# Sway.net
KiCad netlist of a schematic drawn in EAGLE
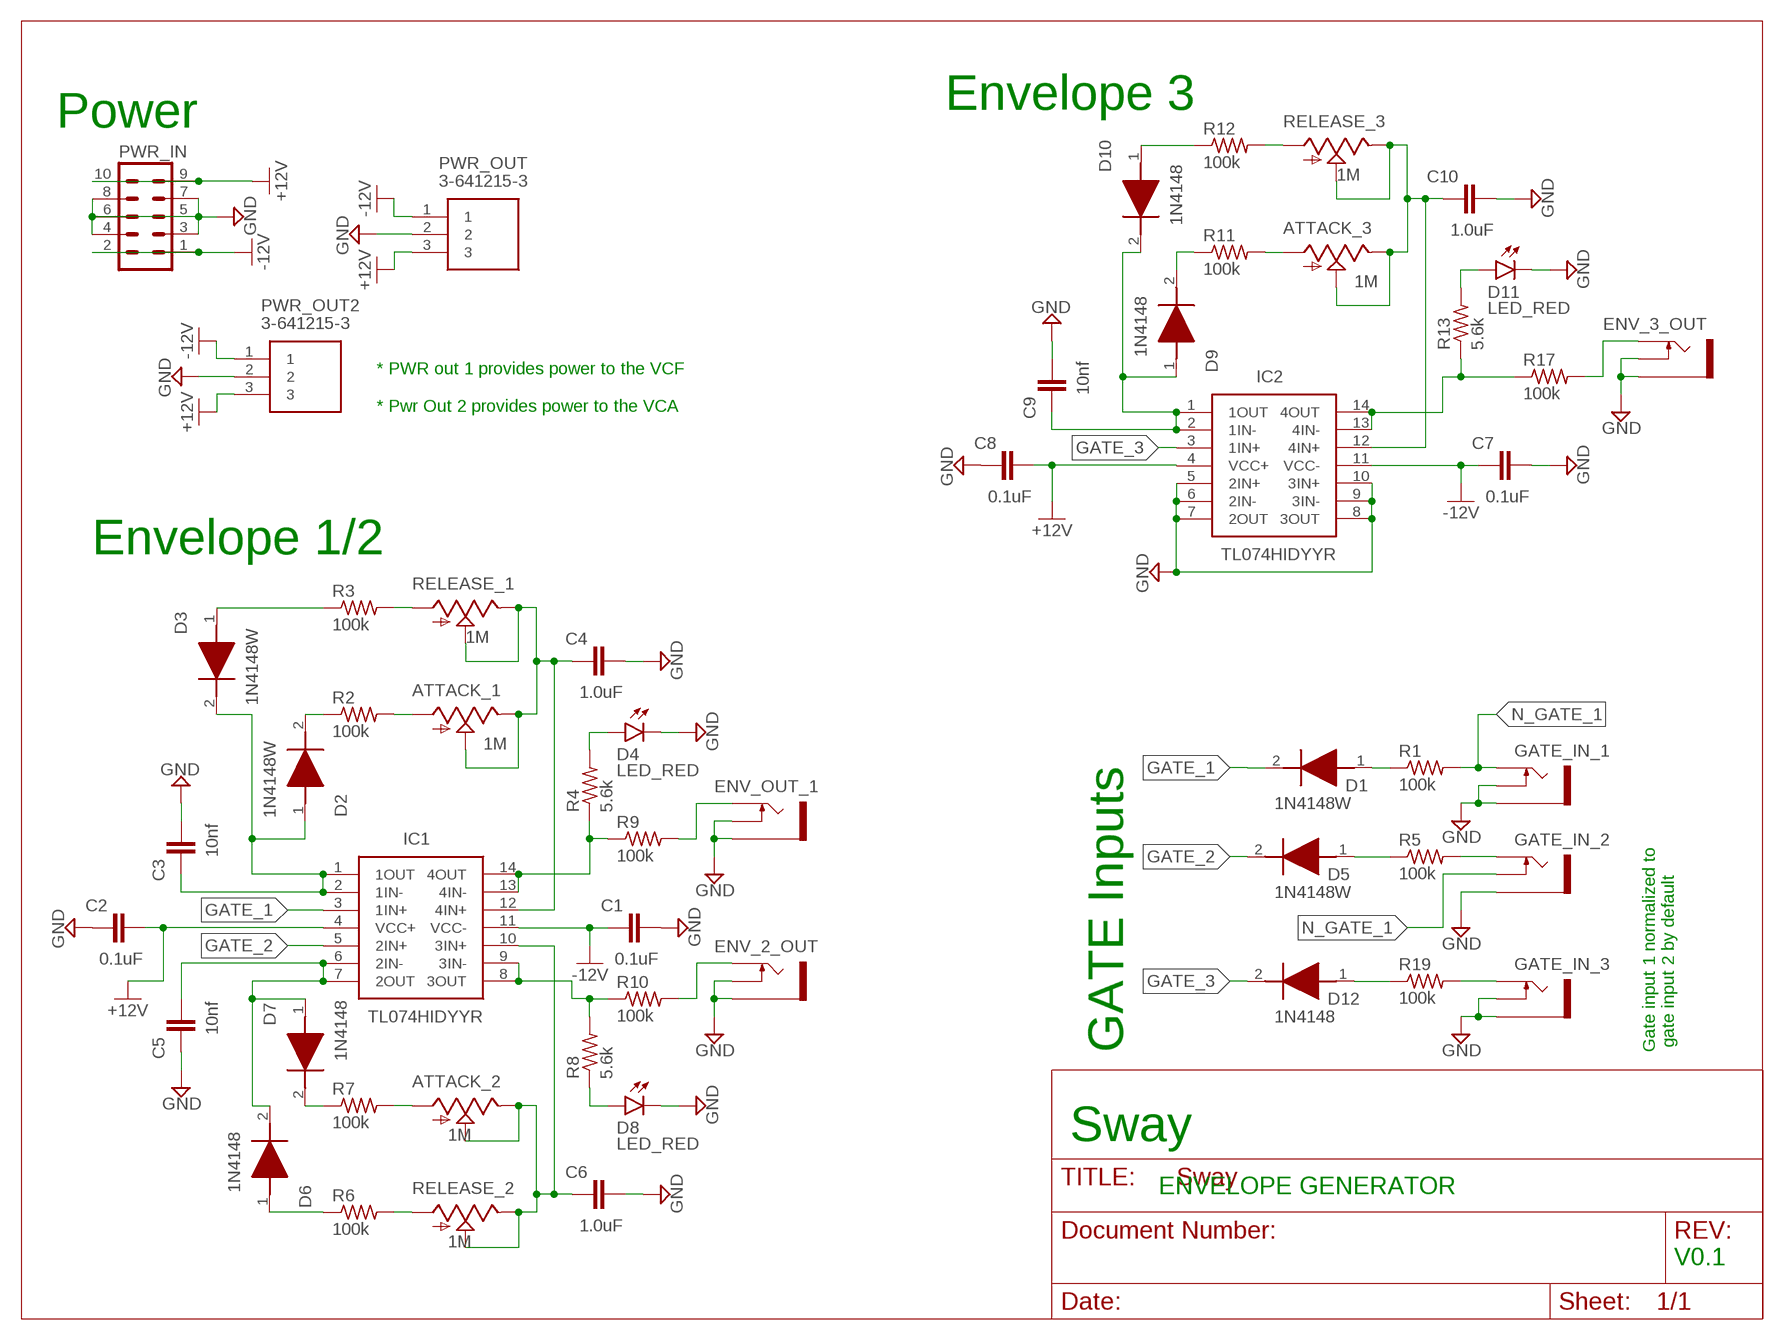
[diagram p0: schematic, sheet 1]

(export (version "E")
  (design (tool "Eeschema 10.0.6"))
  (components
    (comp (ref "ATTACK_1")
      (value "1M")
      (footprint "eagle-import:9MM_SNAP-IN_POT")
      (libsource (lib "eagle-import") (part "9MM_SNAP-IN_POT_"))
    )
    (comp (ref "ATTACK_2")
      (value "1M")
      (footprint "eagle-import:9MM_SNAP-IN_POT")
      (libsource (lib "eagle-import") (part "9MM_SNAP-IN_POT_"))
    )
    (comp (ref "ATTACK_3")
      (value "1M")
      (footprint "eagle-import:9MM_SNAP-IN_POT")
      (libsource (lib "eagle-import") (part "9MM_SNAP-IN_POT_"))
    )
    (comp (ref "C1")
      (value "0.1uF")
      (footprint "eagle-import:0402")
      (libsource (lib "eagle-import") (part "0.1UF-0402-16V-10%"))
    )
    (comp (ref "C2")
      (value "0.1uF")
      (footprint "eagle-import:0402")
      (libsource (lib "eagle-import") (part "0.1UF-0402-16V-10%"))
    )
    (comp (ref "C3")
      (value "10nf")
      (footprint "eagle-import:0402")
      (libsource (lib "eagle-import") (part "0.1UF-0402-16V-10%"))
    )
    (comp (ref "C4")
      (value "1.0uF")
      (footprint "eagle-import:0402")
      (libsource (lib "eagle-import") (part "1.0UF-0402-16V-10%"))
    )
    (comp (ref "C5")
      (value "10nf")
      (footprint "eagle-import:0402")
      (libsource (lib "eagle-import") (part "0.1UF-0402-16V-10%"))
    )
    (comp (ref "C6")
      (value "1.0uF")
      (footprint "eagle-import:0402")
      (libsource (lib "eagle-import") (part "1.0UF-0402-16V-10%"))
    )
    (comp (ref "C7")
      (value "0.1uF")
      (footprint "eagle-import:0402")
      (libsource (lib "eagle-import") (part "0.1UF-0402-16V-10%"))
    )
    (comp (ref "C8")
      (value "0.1uF")
      (footprint "eagle-import:0402")
      (libsource (lib "eagle-import") (part "0.1UF-0402-16V-10%"))
    )
    (comp (ref "C9")
      (value "10nf")
      (footprint "eagle-import:0402")
      (libsource (lib "eagle-import") (part "0.1UF-0402-16V-10%"))
    )
    (comp (ref "C10")
      (value "1.0uF")
      (footprint "eagle-import:0402")
      (libsource (lib "eagle-import") (part "1.0UF-0402-16V-10%"))
    )
    (comp (ref "D1")
      (value "1N4148W")
      (footprint "eagle-import:SOD3716X135N")
      (fields
        (field (name "MANUFACTURER_PART_NUMBER") "1N4148W-HG3_A-08")
        (field (name "MOUSER_PART_NUMBER") "78-1N4148W-HG3_A-08")
      )
      (libsource (lib "eagle-import") (part "1N4148W-HG3_A-08"))
    )
    (comp (ref "D2")
      (value "1N4148W")
      (footprint "eagle-import:SOD3716X135N")
      (fields
        (field (name "MANUFACTURER_PART_NUMBER") "1N4148W-HG3_A-08")
        (field (name "MOUSER_PART_NUMBER") "78-1N4148W-HG3_A-08")
      )
      (libsource (lib "eagle-import") (part "1N4148W-HG3_A-08"))
    )
    (comp (ref "D3")
      (value "1N4148W")
      (footprint "eagle-import:SOD3716X135N")
      (fields
        (field (name "MANUFACTURER_PART_NUMBER") "1N4148W-HG3_A-08")
        (field (name "MOUSER_PART_NUMBER") "78-1N4148W-HG3_A-08")
      )
      (libsource (lib "eagle-import") (part "1N4148W-HG3_A-08"))
    )
    (comp (ref "D4")
      (value "LED_RED")
      (footprint "eagle-import:LEDRD254W60D565H860B")
      (libsource (lib "eagle-import") (part "LED_RADIALRED_"))
    )
    (comp (ref "D5")
      (value "1N4148W")
      (footprint "eagle-import:SOD3716X135N")
      (fields
        (field (name "MANUFACTURER_PART_NUMBER") "1N4148W-HG3_A-08")
        (field (name "MOUSER_PART_NUMBER") "78-1N4148W-HG3_A-08")
      )
      (libsource (lib "eagle-import") (part "1N4148W-HG3_A-08"))
    )
    (comp (ref "D6")
      (value "1N4148")
      (footprint "eagle-import:SOD3716X135N")
      (fields
        (field (name "MANUFACTURER_PART_NUMBER") "1N4148W-HG3_A-08")
        (field (name "MOUSER_PART_NUMBER") "78-1N4148W-HG3_A-08")
      )
      (libsource (lib "eagle-import") (part "1N4148W-HG3_A-08"))
    )
    (comp (ref "D7")
      (value "1N4148")
      (footprint "eagle-import:SOD3716X135N")
      (fields
        (field (name "MANUFACTURER_PART_NUMBER") "1N4148W-HG3_A-08")
        (field (name "MOUSER_PART_NUMBER") "78-1N4148W-HG3_A-08")
      )
      (libsource (lib "eagle-import") (part "1N4148W-HG3_A-08"))
    )
    (comp (ref "D8")
      (value "LED_RED")
      (footprint "eagle-import:LEDRD254W60D565H860B")
      (libsource (lib "eagle-import") (part "LED_RADIALRED_"))
    )
    (comp (ref "D9")
      (value "1N4148")
      (footprint "eagle-import:SOD3716X135N")
      (fields
        (field (name "MANUFACTURER_PART_NUMBER") "1N4148W-HG3_A-08")
        (field (name "MOUSER_PART_NUMBER") "78-1N4148W-HG3_A-08")
      )
      (libsource (lib "eagle-import") (part "1N4148W-HG3_A-08"))
    )
    (comp (ref "D10")
      (value "1N4148")
      (footprint "eagle-import:SOD3716X135N")
      (fields
        (field (name "MANUFACTURER_PART_NUMBER") "1N4148W-HG3_A-08")
        (field (name "MOUSER_PART_NUMBER") "78-1N4148W-HG3_A-08")
      )
      (libsource (lib "eagle-import") (part "1N4148W-HG3_A-08"))
    )
    (comp (ref "D11")
      (value "LED_RED")
      (footprint "eagle-import:LEDRD254W60D565H860B")
      (libsource (lib "eagle-import") (part "LED_RADIALRED_"))
    )
    (comp (ref "D12")
      (value "1N4148")
      (footprint "eagle-import:SOD3716X135N")
      (fields
        (field (name "MANUFACTURER_PART_NUMBER") "1N4148W-HG3_A-08")
        (field (name "MOUSER_PART_NUMBER") "78-1N4148W-HG3_A-08")
      )
      (libsource (lib "eagle-import") (part "1N4148W-HG3_A-08"))
    )
    (comp (ref "ENV_2_OUT")
      (value "THONKICONNNEW")
      (footprint "eagle-import:WQP-PJ301M-12_JACK")
      (fields
        (field (name "SPICEMODEL") "GATE_IN_1")
        (field (name "SPICEMODELTEXT") "**********************\\n* Autodesk EAGLE - SPICE Model File\\n* Author:\\n* Date: \\n**********************\\n.SUBCKT GATE_IN_1 T S SW\\n* Assume normally closed switch (SW → T when unplugged)\\n* Always connect sleeve\\nRsleeve S 0 0.001\\n* Connect switch to tip if no plug\\nRnorm SW T 1\\n* Patch cable overrides switch (comment one of these in/out based on mode)\\nRpatched TIP_SRC T 0.001\\n.ENDS GATE_IN_1")
        (field (name "SPICEPREFIX") "X")
      )
      (libsource (lib "eagle-import") (part "THONKICONNNEW"))
    )
    (comp (ref "ENV_3_OUT")
      (value "THONKICONNNEW")
      (footprint "eagle-import:WQP-PJ301M-12_JACK")
      (fields
        (field (name "SPICEMODEL") "GATE_IN_1")
        (field (name "SPICEMODELTEXT") "**********************\\n* Autodesk EAGLE - SPICE Model File\\n* Author:\\n* Date: \\n**********************\\n.SUBCKT GATE_IN_1 T S SW\\n* Assume normally closed switch (SW → T when unplugged)\\n* Always connect sleeve\\nRsleeve S 0 0.001\\n* Connect switch to tip if no plug\\nRnorm SW T 1\\n* Patch cable overrides switch (comment one of these in/out based on mode)\\nRpatched TIP_SRC T 0.001\\n.ENDS GATE_IN_1")
        (field (name "SPICEPREFIX") "X")
      )
      (libsource (lib "eagle-import") (part "THONKICONNNEW"))
    )
    (comp (ref "ENV_OUT_1")
      (value "THONKICONNNEW")
      (footprint "eagle-import:WQP-PJ301M-12_JACK")
      (libsource (lib "eagle-import") (part "THONKICONNNEW"))
    )
    (comp (ref "GATE_IN_1")
      (value "THONKICONNNEW")
      (footprint "eagle-import:WQP-PJ301M-12_JACK")
      (fields
        (field (name "SPICEMODEL") "GATE_IN_1")
        (field (name "SPICEMODELTEXT") "**********************\\n* Autodesk EAGLE - SPICE Model File\\n* Author:\\n* Date: \\n**********************\\n.SUBCKT GATE_IN_1 T S SW\\n* Assume normally closed switch (SW → T when unplugged)\\n* Always connect sleeve\\nRsleeve S 0 0.001\\n* Connect switch to tip if no plug\\nRnorm SW T 1\\n* Patch cable overrides switch (comment one of these in/out based on mode)\\nRpatched TIP_SRC T 0.001\\n.ENDS GATE_IN_1")
        (field (name "SPICEPREFIX") "X")
      )
      (libsource (lib "eagle-import") (part "THONKICONNNEW"))
    )
    (comp (ref "GATE_IN_2")
      (value "THONKICONNNEW")
      (footprint "eagle-import:WQP-PJ301M-12_JACK")
      (fields
        (field (name "SPICEMODEL") "GATE_IN_1")
        (field (name "SPICEMODELTEXT") "**********************\\n* Autodesk EAGLE - SPICE Model File\\n* Author:\\n* Date: \\n**********************\\n.SUBCKT GATE_IN_1 T S SW\\n* Assume normally closed switch (SW → T when unplugged)\\n* Always connect sleeve\\nRsleeve S 0 0.001\\n* Connect switch to tip if no plug\\nRnorm SW T 1\\n* Patch cable overrides switch (comment one of these in/out based on mode)\\nRpatched TIP_SRC T 0.001\\n.ENDS GATE_IN_1")
        (field (name "SPICEPREFIX") "X")
      )
      (libsource (lib "eagle-import") (part "THONKICONNNEW"))
    )
    (comp (ref "GATE_IN_3")
      (value "THONKICONNNEW")
      (footprint "eagle-import:WQP-PJ301M-12_JACK")
      (fields
        (field (name "SPICEMODEL") "GATE_IN_1")
        (field (name "SPICEMODELTEXT") "**********************\\n* Autodesk EAGLE - SPICE Model File\\n* Author:\\n* Date: \\n**********************\\n.SUBCKT GATE_IN_1 T S SW\\n* Assume normally closed switch (SW → T when unplugged)\\n* Always connect sleeve\\nRsleeve S 0 0.001\\n* Connect switch to tip if no plug\\nRnorm SW T 1\\n* Patch cable overrides switch (comment one of these in/out based on mode)\\nRpatched TIP_SRC T 0.001\\n.ENDS GATE_IN_1")
        (field (name "SPICEPREFIX") "X")
      )
      (libsource (lib "eagle-import") (part "THONKICONNNEW"))
    )
    (comp (ref "IC1")
      (value "TL074HIDYYR")
      (footprint "eagle-import:SOP50P326X110-14N")
      (fields (field (name "MOUSER_PART_NUMBER") "595-TL074HIDYYR"))
      (libsource (lib "eagle-import") (part "TL074HIDYYR"))
    )
    (comp (ref "IC2")
      (value "TL074HIDYYR")
      (footprint "eagle-import:SOP50P326X110-14N")
      (fields (field (name "MOUSER_PART_NUMBER") "595-TL074HIDYYR"))
      (libsource (lib "eagle-import") (part "TL074HIDYYR"))
    )
    (comp (ref "PWR_IN")
      (value "EURO_POWER_HEADERREGULAR")
      (footprint "eagle-import:EURO_POWER_HEADER")
      (libsource (lib "eagle-import") (part "EURO_POWER_HEADERREGULAR"))
    )
    (comp (ref "PWR_OUT")
      (value "3-641215-3")
      (footprint "eagle-import:SHDR3W66P0X254_1X3_762X572X104")
      (fields
        (field (name "MOUSER_PART_NUMBER") "571-3-641215-3")
        (field (name "SPICEMODEL") "PWR_OUT")
        (field (name "SPICEMODELTEXT") "**********************\\n* Autodesk EAGLE - SPICE Model File\\n* Author:\\n* Date: \\n**********************\\n.SUBCKT PWR_OUT 1 2 3\\n* Pin 1 = -12V\\n* Pin 2 = GND\\n* Pin 3 = +12V\\n* Tie pins to global rails\\nRout1 1 VNEG 0.001\\nRout2 2 0   0.001\\nRout3 3 VPOS 0.001\\n.ENDS PWR_OUT")
        (field (name "SPICEPREFIX") "X")
      )
      (libsource (lib "eagle-import") (part "3-641215-3"))
    )
    (comp (ref "PWR_OUT2")
      (value "3-641215-3")
      (footprint "eagle-import:SHDR3W66P0X254_1X3_762X572X104")
      (fields
        (field (name "MOUSER_PART_NUMBER") "571-3-641215-3")
        (field (name "SPICEMODEL") "PWR_OUT")
        (field (name "SPICEMODELTEXT") "**********************\\n* Autodesk EAGLE - SPICE Model File\\n* Author:\\n* Date: \\n**********************\\n.SUBCKT PWR_OUT 1 2 3\\n* Pin 1 = -12V\\n* Pin 2 = GND\\n* Pin 3 = +12V\\n* Tie pins to global rails\\nRout1 1 VNEG 0.001\\nRout2 2 0   0.001\\nRout3 3 VPOS 0.001\\n.ENDS PWR_OUT")
        (field (name "SPICEPREFIX") "X")
      )
      (libsource (lib "eagle-import") (part "3-641215-3"))
    )
    (comp (ref "R1")
      (value "100k")
      (footprint "eagle-import:RESC1005X40")
      (libsource (lib "eagle-import") (part "R-USCHIP-0402(1005-METRIC)_"))
    )
    (comp (ref "R2")
      (value "100k")
      (footprint "eagle-import:RESC1005X40")
      (libsource (lib "eagle-import") (part "R-USCHIP-0402(1005-METRIC)_"))
    )
    (comp (ref "R3")
      (value "100k")
      (footprint "eagle-import:RESC1005X40")
      (libsource (lib "eagle-import") (part "R-USCHIP-0402(1005-METRIC)_"))
    )
    (comp (ref "R4")
      (value "5.6k")
      (footprint "eagle-import:RESC1005X40")
      (libsource (lib "eagle-import") (part "R-USCHIP-0402(1005-METRIC)_"))
    )
    (comp (ref "R5")
      (value "100k")
      (footprint "eagle-import:RESC1005X40")
      (libsource (lib "eagle-import") (part "R-USCHIP-0402(1005-METRIC)_"))
    )
    (comp (ref "R6")
      (value "100k")
      (footprint "eagle-import:RESC1005X40")
      (libsource (lib "eagle-import") (part "R-USCHIP-0402(1005-METRIC)_"))
    )
    (comp (ref "R7")
      (value "100k")
      (footprint "eagle-import:RESC1005X40")
      (libsource (lib "eagle-import") (part "R-USCHIP-0402(1005-METRIC)_"))
    )
    (comp (ref "R8")
      (value "5.6k")
      (footprint "eagle-import:RESC1005X40")
      (libsource (lib "eagle-import") (part "R-USCHIP-0402(1005-METRIC)_"))
    )
    (comp (ref "R9")
      (value "100k")
      (footprint "eagle-import:RESC1005X40")
      (libsource (lib "eagle-import") (part "R-USCHIP-0402(1005-METRIC)_"))
    )
    (comp (ref "R10")
      (value "100k")
      (footprint "eagle-import:RESC1005X40")
      (libsource (lib "eagle-import") (part "R-USCHIP-0402(1005-METRIC)_"))
    )
    (comp (ref "R11")
      (value "100k")
      (footprint "eagle-import:RESC1005X40")
      (libsource (lib "eagle-import") (part "R-USCHIP-0402(1005-METRIC)_"))
    )
    (comp (ref "R12")
      (value "100k")
      (footprint "eagle-import:RESC1005X40")
      (libsource (lib "eagle-import") (part "R-USCHIP-0402(1005-METRIC)_"))
    )
    (comp (ref "R13")
      (value "5.6k")
      (footprint "eagle-import:RESC1005X40")
      (libsource (lib "eagle-import") (part "R-USCHIP-0402(1005-METRIC)_"))
    )
    (comp (ref "R17")
      (value "100k")
      (footprint "eagle-import:RESC1005X40")
      (libsource (lib "eagle-import") (part "R-USCHIP-0402(1005-METRIC)_"))
    )
    (comp (ref "R19")
      (value "100k")
      (footprint "eagle-import:RESC1005X40")
      (libsource (lib "eagle-import") (part "R-USCHIP-0402(1005-METRIC)_"))
    )
    (comp (ref "RELEASE_1")
      (value "1M")
      (footprint "eagle-import:9MM_SNAP-IN_POT")
      (libsource (lib "eagle-import") (part "9MM_SNAP-IN_POT_"))
    )
    (comp (ref "RELEASE_2")
      (value "1M")
      (footprint "eagle-import:9MM_SNAP-IN_POT")
      (libsource (lib "eagle-import") (part "9MM_SNAP-IN_POT_"))
    )
    (comp (ref "RELEASE_3")
      (value "1M")
      (footprint "eagle-import:9MM_SNAP-IN_POT")
      (libsource (lib "eagle-import") (part "9MM_SNAP-IN_POT_"))
    )
  )
  (nets
    (net (code "1") (name "+12V") (class "Default")
      (node (ref "C2") (pin "2") (pinfunction "2_2") (pintype "passive"))
      (node (ref "C8") (pin "2") (pinfunction "2_2") (pintype "passive"))
      (node (ref "IC1") (pin "4") (pinfunction "VCC+_4") (pintype "bidirectional"))
      (node (ref "IC2") (pin "4") (pinfunction "VCC+_4") (pintype "bidirectional"))
      (node (ref "PWR_IN") (pin "10") (pinfunction "10_10") (pintype "passive"))
      (node (ref "PWR_IN") (pin "9") (pinfunction "9_9") (pintype "passive"))
      (node (ref "PWR_OUT") (pin "3") (pinfunction "3_3") (pintype "bidirectional"))
      (node (ref "PWR_OUT2") (pin "3") (pinfunction "3_3") (pintype "bidirectional"))
    )
    (net (code "2") (name "-12V") (class "Default")
      (node (ref "C1") (pin "1") (pinfunction "1_1") (pintype "passive"))
      (node (ref "C7") (pin "1") (pinfunction "1_1") (pintype "passive"))
      (node (ref "IC1") (pin "11") (pinfunction "VCC-_11") (pintype "bidirectional"))
      (node (ref "IC2") (pin "11") (pinfunction "VCC-_11") (pintype "bidirectional"))
      (node (ref "PWR_IN") (pin "1") (pinfunction "1_1") (pintype "passive"))
      (node (ref "PWR_IN") (pin "2") (pinfunction "2_2") (pintype "passive"))
      (node (ref "PWR_OUT") (pin "1") (pinfunction "1_1") (pintype "bidirectional"))
      (node (ref "PWR_OUT2") (pin "1") (pinfunction "1_1") (pintype "bidirectional"))
    )
    (net (code "3") (name "GATE_1") (class "Default")
      (node (ref "D1") (pin "2") (pinfunction "K_2") (pintype "bidirectional"))
      (node (ref "IC1") (pin "3") (pinfunction "1IN+_3") (pintype "bidirectional"))
    )
    (net (code "4") (name "GATE_2") (class "Default")
      (node (ref "D5") (pin "2") (pinfunction "K_2") (pintype "bidirectional"))
      (node (ref "IC1") (pin "5") (pinfunction "2IN+_5") (pintype "bidirectional"))
    )
    (net (code "5") (name "GATE_3") (class "Default")
      (node (ref "D12") (pin "2") (pinfunction "K_2") (pintype "bidirectional"))
      (node (ref "IC2") (pin "3") (pinfunction "1IN+_3") (pintype "bidirectional"))
    )
    (net (code "6") (name "GND") (class "Default")
      (node (ref "C1") (pin "2") (pinfunction "2_2") (pintype "passive"))
      (node (ref "C10") (pin "2") (pinfunction "2_2") (pintype "passive"))
      (node (ref "C2") (pin "1") (pinfunction "1_1") (pintype "passive"))
      (node (ref "C3") (pin "2") (pinfunction "2_2") (pintype "passive"))
      (node (ref "C4") (pin "2") (pinfunction "2_2") (pintype "passive"))
      (node (ref "C5") (pin "1") (pinfunction "1_1") (pintype "passive"))
      (node (ref "C6") (pin "2") (pinfunction "2_2") (pintype "passive"))
      (node (ref "C7") (pin "2") (pinfunction "2_2") (pintype "passive"))
      (node (ref "C8") (pin "1") (pinfunction "1_1") (pintype "passive"))
      (node (ref "C9") (pin "2") (pinfunction "2_2") (pintype "passive"))
      (node (ref "D11") (pin "2") (pinfunction "C_2") (pintype "passive"))
      (node (ref "D4") (pin "2") (pinfunction "C_2") (pintype "passive"))
      (node (ref "D8") (pin "2") (pinfunction "C_2") (pintype "passive"))
      (node (ref "ENV_2_OUT") (pin "P$2_SWITCH") (pinfunction "SWITCH_P$2_SWITCH") (pintype "passive"))
      (node (ref "ENV_2_OUT") (pin "P$3_SLEEVE") (pinfunction "SLEEVE_P$3_SLEEVE") (pintype "passive"))
      (node (ref "ENV_3_OUT") (pin "P$2_SWITCH") (pinfunction "SWITCH_P$2_SWITCH") (pintype "passive"))
      (node (ref "ENV_3_OUT") (pin "P$3_SLEEVE") (pinfunction "SLEEVE_P$3_SLEEVE") (pintype "passive"))
      (node (ref "ENV_OUT_1") (pin "P$2_SWITCH") (pinfunction "SWITCH_P$2_SWITCH") (pintype "passive"))
      (node (ref "ENV_OUT_1") (pin "P$3_SLEEVE") (pinfunction "SLEEVE_P$3_SLEEVE") (pintype "passive"))
      (node (ref "GATE_IN_1") (pin "P$2_SWITCH") (pinfunction "SWITCH_P$2_SWITCH") (pintype "passive"))
      (node (ref "GATE_IN_1") (pin "P$3_SLEEVE") (pinfunction "SLEEVE_P$3_SLEEVE") (pintype "passive"))
      (node (ref "GATE_IN_2") (pin "P$3_SLEEVE") (pinfunction "SLEEVE_P$3_SLEEVE") (pintype "passive"))
      (node (ref "GATE_IN_3") (pin "P$2_SWITCH") (pinfunction "SWITCH_P$2_SWITCH") (pintype "passive"))
      (node (ref "GATE_IN_3") (pin "P$3_SLEEVE") (pinfunction "SLEEVE_P$3_SLEEVE") (pintype "passive"))
      (node (ref "IC2") (pin "10") (pinfunction "3IN+_10") (pintype "bidirectional"))
      (node (ref "IC2") (pin "5") (pinfunction "2IN+_5") (pintype "bidirectional"))
      (node (ref "IC2") (pin "6") (pinfunction "2IN-_6") (pintype "bidirectional"))
      (node (ref "IC2") (pin "7") (pinfunction "2OUT_7") (pintype "bidirectional"))
      (node (ref "IC2") (pin "8") (pinfunction "3OUT_8") (pintype "bidirectional"))
      (node (ref "IC2") (pin "9") (pinfunction "3IN-_9") (pintype "bidirectional"))
      (node (ref "PWR_IN") (pin "3") (pinfunction "3_3") (pintype "passive"))
      (node (ref "PWR_IN") (pin "4") (pinfunction "4_4") (pintype "passive"))
      (node (ref "PWR_IN") (pin "5") (pinfunction "5_5") (pintype "passive"))
      (node (ref "PWR_IN") (pin "6") (pinfunction "6_6") (pintype "passive"))
      (node (ref "PWR_IN") (pin "7") (pinfunction "7_7") (pintype "passive"))
      (node (ref "PWR_IN") (pin "8") (pinfunction "8_8") (pintype "passive"))
      (node (ref "PWR_OUT") (pin "2") (pinfunction "2_2") (pintype "bidirectional"))
      (node (ref "PWR_OUT2") (pin "2") (pinfunction "2_2") (pintype "bidirectional"))
    )
    (net (code "7") (name "N_GATE_1") (class "Default")
      (node (ref "GATE_IN_1") (pin "P$1_TIP") (pinfunction "TIP_P$1_TIP") (pintype "passive"))
      (node (ref "GATE_IN_2") (pin "P$2_SWITCH") (pinfunction "SWITCH_P$2_SWITCH") (pintype "passive"))
      (node (ref "R1") (pin "2") (pinfunction "2_2") (pintype "passive"))
    )
    (net (code "8") (name "Net-(ATTACK_1-A)") (class "Default")
      (node (ref "ATTACK_1") (pin "1") (pinfunction "A_1") (pintype "passive"))
      (node (ref "R2") (pin "2") (pinfunction "2_2") (pintype "passive"))
    )
    (net (code "9") (name "Net-(ATTACK_1-E)") (class "Default")
      (node (ref "ATTACK_1") (pin "2") (pinfunction "S_2") (pintype "passive"))
      (node (ref "ATTACK_1") (pin "3") (pinfunction "E_3") (pintype "passive"))
      (node (ref "C4") (pin "1") (pinfunction "1_1") (pintype "passive"))
      (node (ref "IC1") (pin "12") (pinfunction "4IN+_12") (pintype "bidirectional"))
      (node (ref "RELEASE_1") (pin "2") (pinfunction "S_2") (pintype "passive"))
      (node (ref "RELEASE_1") (pin "3") (pinfunction "E_3") (pintype "passive"))
    )
    (net (code "10") (name "Net-(ATTACK_2-A)") (class "Default")
      (node (ref "ATTACK_2") (pin "1") (pinfunction "A_1") (pintype "passive"))
      (node (ref "R7") (pin "2") (pinfunction "2_2") (pintype "passive"))
    )
    (net (code "11") (name "Net-(ATTACK_2-E)") (class "Default")
      (node (ref "ATTACK_2") (pin "2") (pinfunction "S_2") (pintype "passive"))
      (node (ref "ATTACK_2") (pin "3") (pinfunction "E_3") (pintype "passive"))
      (node (ref "C6") (pin "1") (pinfunction "1_1") (pintype "passive"))
      (node (ref "IC1") (pin "10") (pinfunction "3IN+_10") (pintype "bidirectional"))
      (node (ref "RELEASE_2") (pin "2") (pinfunction "S_2") (pintype "passive"))
      (node (ref "RELEASE_2") (pin "3") (pinfunction "E_3") (pintype "passive"))
    )
    (net (code "12") (name "Net-(ATTACK_3-A)") (class "Default")
      (node (ref "ATTACK_3") (pin "1") (pinfunction "A_1") (pintype "passive"))
      (node (ref "R11") (pin "2") (pinfunction "2_2") (pintype "passive"))
    )
    (net (code "13") (name "Net-(ATTACK_3-E)") (class "Default")
      (node (ref "ATTACK_3") (pin "2") (pinfunction "S_2") (pintype "passive"))
      (node (ref "ATTACK_3") (pin "3") (pinfunction "E_3") (pintype "passive"))
      (node (ref "C10") (pin "1") (pinfunction "1_1") (pintype "passive"))
      (node (ref "IC2") (pin "12") (pinfunction "4IN+_12") (pintype "bidirectional"))
      (node (ref "RELEASE_3") (pin "2") (pinfunction "S_2") (pintype "passive"))
      (node (ref "RELEASE_3") (pin "3") (pinfunction "E_3") (pintype "passive"))
    )
    (net (code "14") (name "Net-(D1-A)") (class "Default")
      (node (ref "D1") (pin "1") (pinfunction "A_1") (pintype "bidirectional"))
      (node (ref "R1") (pin "1") (pinfunction "1_1") (pintype "passive"))
    )
    (net (code "15") (name "Net-(D2-A)") (class "Default")
      (node (ref "C3") (pin "1") (pinfunction "1_1") (pintype "passive"))
      (node (ref "D2") (pin "1") (pinfunction "A_1") (pintype "bidirectional"))
      (node (ref "D3") (pin "2") (pinfunction "K_2") (pintype "bidirectional"))
      (node (ref "IC1") (pin "1") (pinfunction "1OUT_1") (pintype "bidirectional"))
      (node (ref "IC1") (pin "2") (pinfunction "1IN-_2") (pintype "bidirectional"))
    )
    (net (code "16") (name "Net-(D2-K)") (class "Default")
      (node (ref "D2") (pin "2") (pinfunction "K_2") (pintype "bidirectional"))
      (node (ref "R2") (pin "1") (pinfunction "1_1") (pintype "passive"))
    )
    (net (code "17") (name "Net-(D3-A)") (class "Default")
      (node (ref "D3") (pin "1") (pinfunction "A_1") (pintype "bidirectional"))
      (node (ref "R3") (pin "1") (pinfunction "1_1") (pintype "passive"))
    )
    (net (code "18") (name "Net-(D4-A)") (class "Default")
      (node (ref "D4") (pin "1") (pinfunction "A_1") (pintype "passive"))
      (node (ref "R4") (pin "2") (pinfunction "2_2") (pintype "passive"))
    )
    (net (code "19") (name "Net-(D5-A)") (class "Default")
      (node (ref "D5") (pin "1") (pinfunction "A_1") (pintype "bidirectional"))
      (node (ref "R5") (pin "1") (pinfunction "1_1") (pintype "passive"))
    )
    (net (code "20") (name "Net-(D6-A)") (class "Default")
      (node (ref "D6") (pin "1") (pinfunction "A_1") (pintype "bidirectional"))
      (node (ref "R6") (pin "1") (pinfunction "1_1") (pintype "passive"))
    )
    (net (code "21") (name "Net-(D6-K)") (class "Default")
      (node (ref "C5") (pin "2") (pinfunction "2_2") (pintype "passive"))
      (node (ref "D6") (pin "2") (pinfunction "K_2") (pintype "bidirectional"))
      (node (ref "D7") (pin "1") (pinfunction "A_1") (pintype "bidirectional"))
      (node (ref "IC1") (pin "6") (pinfunction "2IN-_6") (pintype "bidirectional"))
      (node (ref "IC1") (pin "7") (pinfunction "2OUT_7") (pintype "bidirectional"))
    )
    (net (code "22") (name "Net-(D7-K)") (class "Default")
      (node (ref "D7") (pin "2") (pinfunction "K_2") (pintype "bidirectional"))
      (node (ref "R7") (pin "1") (pinfunction "1_1") (pintype "passive"))
    )
    (net (code "23") (name "Net-(D8-A)") (class "Default")
      (node (ref "D8") (pin "1") (pinfunction "A_1") (pintype "passive"))
      (node (ref "R8") (pin "1") (pinfunction "1_1") (pintype "passive"))
    )
    (net (code "24") (name "Net-(D9-K)") (class "Default")
      (node (ref "D9") (pin "2") (pinfunction "K_2") (pintype "bidirectional"))
      (node (ref "R11") (pin "1") (pinfunction "1_1") (pintype "passive"))
    )
    (net (code "25") (name "Net-(D10-A)") (class "Default")
      (node (ref "D10") (pin "1") (pinfunction "A_1") (pintype "bidirectional"))
      (node (ref "R12") (pin "1") (pinfunction "1_1") (pintype "passive"))
    )
    (net (code "26") (name "Net-(D10-K)") (class "Default")
      (node (ref "C9") (pin "1") (pinfunction "1_1") (pintype "passive"))
      (node (ref "D10") (pin "2") (pinfunction "K_2") (pintype "bidirectional"))
      (node (ref "D9") (pin "1") (pinfunction "A_1") (pintype "bidirectional"))
      (node (ref "IC2") (pin "1") (pinfunction "1OUT_1") (pintype "bidirectional"))
      (node (ref "IC2") (pin "2") (pinfunction "1IN-_2") (pintype "bidirectional"))
    )
    (net (code "27") (name "Net-(D11-A)") (class "Default")
      (node (ref "D11") (pin "1") (pinfunction "A_1") (pintype "passive"))
      (node (ref "R13") (pin "2") (pinfunction "2_2") (pintype "passive"))
    )
    (net (code "28") (name "Net-(D12-A)") (class "Default")
      (node (ref "D12") (pin "1") (pinfunction "A_1") (pintype "bidirectional"))
      (node (ref "R19") (pin "1") (pinfunction "1_1") (pintype "passive"))
    )
    (net (code "29") (name "Net-(ENV_2_OUT-TIP)") (class "Default")
      (node (ref "ENV_2_OUT") (pin "P$1_TIP") (pinfunction "TIP_P$1_TIP") (pintype "passive"))
      (node (ref "R10") (pin "2") (pinfunction "2_2") (pintype "passive"))
    )
    (net (code "30") (name "Net-(ENV_3_OUT-TIP)") (class "Default")
      (node (ref "ENV_3_OUT") (pin "P$1_TIP") (pinfunction "TIP_P$1_TIP") (pintype "passive"))
      (node (ref "R17") (pin "2") (pinfunction "2_2") (pintype "passive"))
    )
    (net (code "31") (name "Net-(ENV_OUT_1-TIP)") (class "Default")
      (node (ref "ENV_OUT_1") (pin "P$1_TIP") (pinfunction "TIP_P$1_TIP") (pintype "passive"))
      (node (ref "R9") (pin "2") (pinfunction "2_2") (pintype "passive"))
    )
    (net (code "32") (name "Net-(GATE_IN_2-TIP)") (class "Default")
      (node (ref "GATE_IN_2") (pin "P$1_TIP") (pinfunction "TIP_P$1_TIP") (pintype "passive"))
      (node (ref "R5") (pin "2") (pinfunction "2_2") (pintype "passive"))
    )
    (net (code "33") (name "Net-(GATE_IN_3-TIP)") (class "Default")
      (node (ref "GATE_IN_3") (pin "P$1_TIP") (pinfunction "TIP_P$1_TIP") (pintype "passive"))
      (node (ref "R19") (pin "2") (pinfunction "2_2") (pintype "passive"))
    )
    (net (code "34") (name "Net-(IC1-3IN-)") (class "Default")
      (node (ref "IC1") (pin "8") (pinfunction "3OUT_8") (pintype "bidirectional"))
      (node (ref "IC1") (pin "9") (pinfunction "3IN-_9") (pintype "bidirectional"))
      (node (ref "R10") (pin "1") (pinfunction "1_1") (pintype "passive"))
      (node (ref "R8") (pin "2") (pinfunction "2_2") (pintype "passive"))
    )
    (net (code "35") (name "Net-(IC1-4IN-)") (class "Default")
      (node (ref "IC1") (pin "13") (pinfunction "4IN-_13") (pintype "bidirectional"))
      (node (ref "IC1") (pin "14") (pinfunction "4OUT_14") (pintype "bidirectional"))
      (node (ref "R4") (pin "1") (pinfunction "1_1") (pintype "passive"))
      (node (ref "R9") (pin "1") (pinfunction "1_1") (pintype "passive"))
    )
    (net (code "36") (name "Net-(IC2-4IN-)") (class "Default")
      (node (ref "IC2") (pin "13") (pinfunction "4IN-_13") (pintype "bidirectional"))
      (node (ref "IC2") (pin "14") (pinfunction "4OUT_14") (pintype "bidirectional"))
      (node (ref "R13") (pin "1") (pinfunction "1_1") (pintype "passive"))
      (node (ref "R17") (pin "1") (pinfunction "1_1") (pintype "passive"))
    )
    (net (code "37") (name "Net-(RELEASE_1-A)") (class "Default")
      (node (ref "R3") (pin "2") (pinfunction "2_2") (pintype "passive"))
      (node (ref "RELEASE_1") (pin "1") (pinfunction "A_1") (pintype "passive"))
    )
    (net (code "38") (name "Net-(RELEASE_2-A)") (class "Default")
      (node (ref "R6") (pin "2") (pinfunction "2_2") (pintype "passive"))
      (node (ref "RELEASE_2") (pin "1") (pinfunction "A_1") (pintype "passive"))
    )
    (net (code "39") (name "Net-(RELEASE_3-A)") (class "Default")
      (node (ref "R12") (pin "2") (pinfunction "2_2") (pintype "passive"))
      (node (ref "RELEASE_3") (pin "1") (pinfunction "A_1") (pintype "passive"))
    )
  )
)
